# Sheet1.net
KiCad netlist of a schematic drawn in Altium Designer
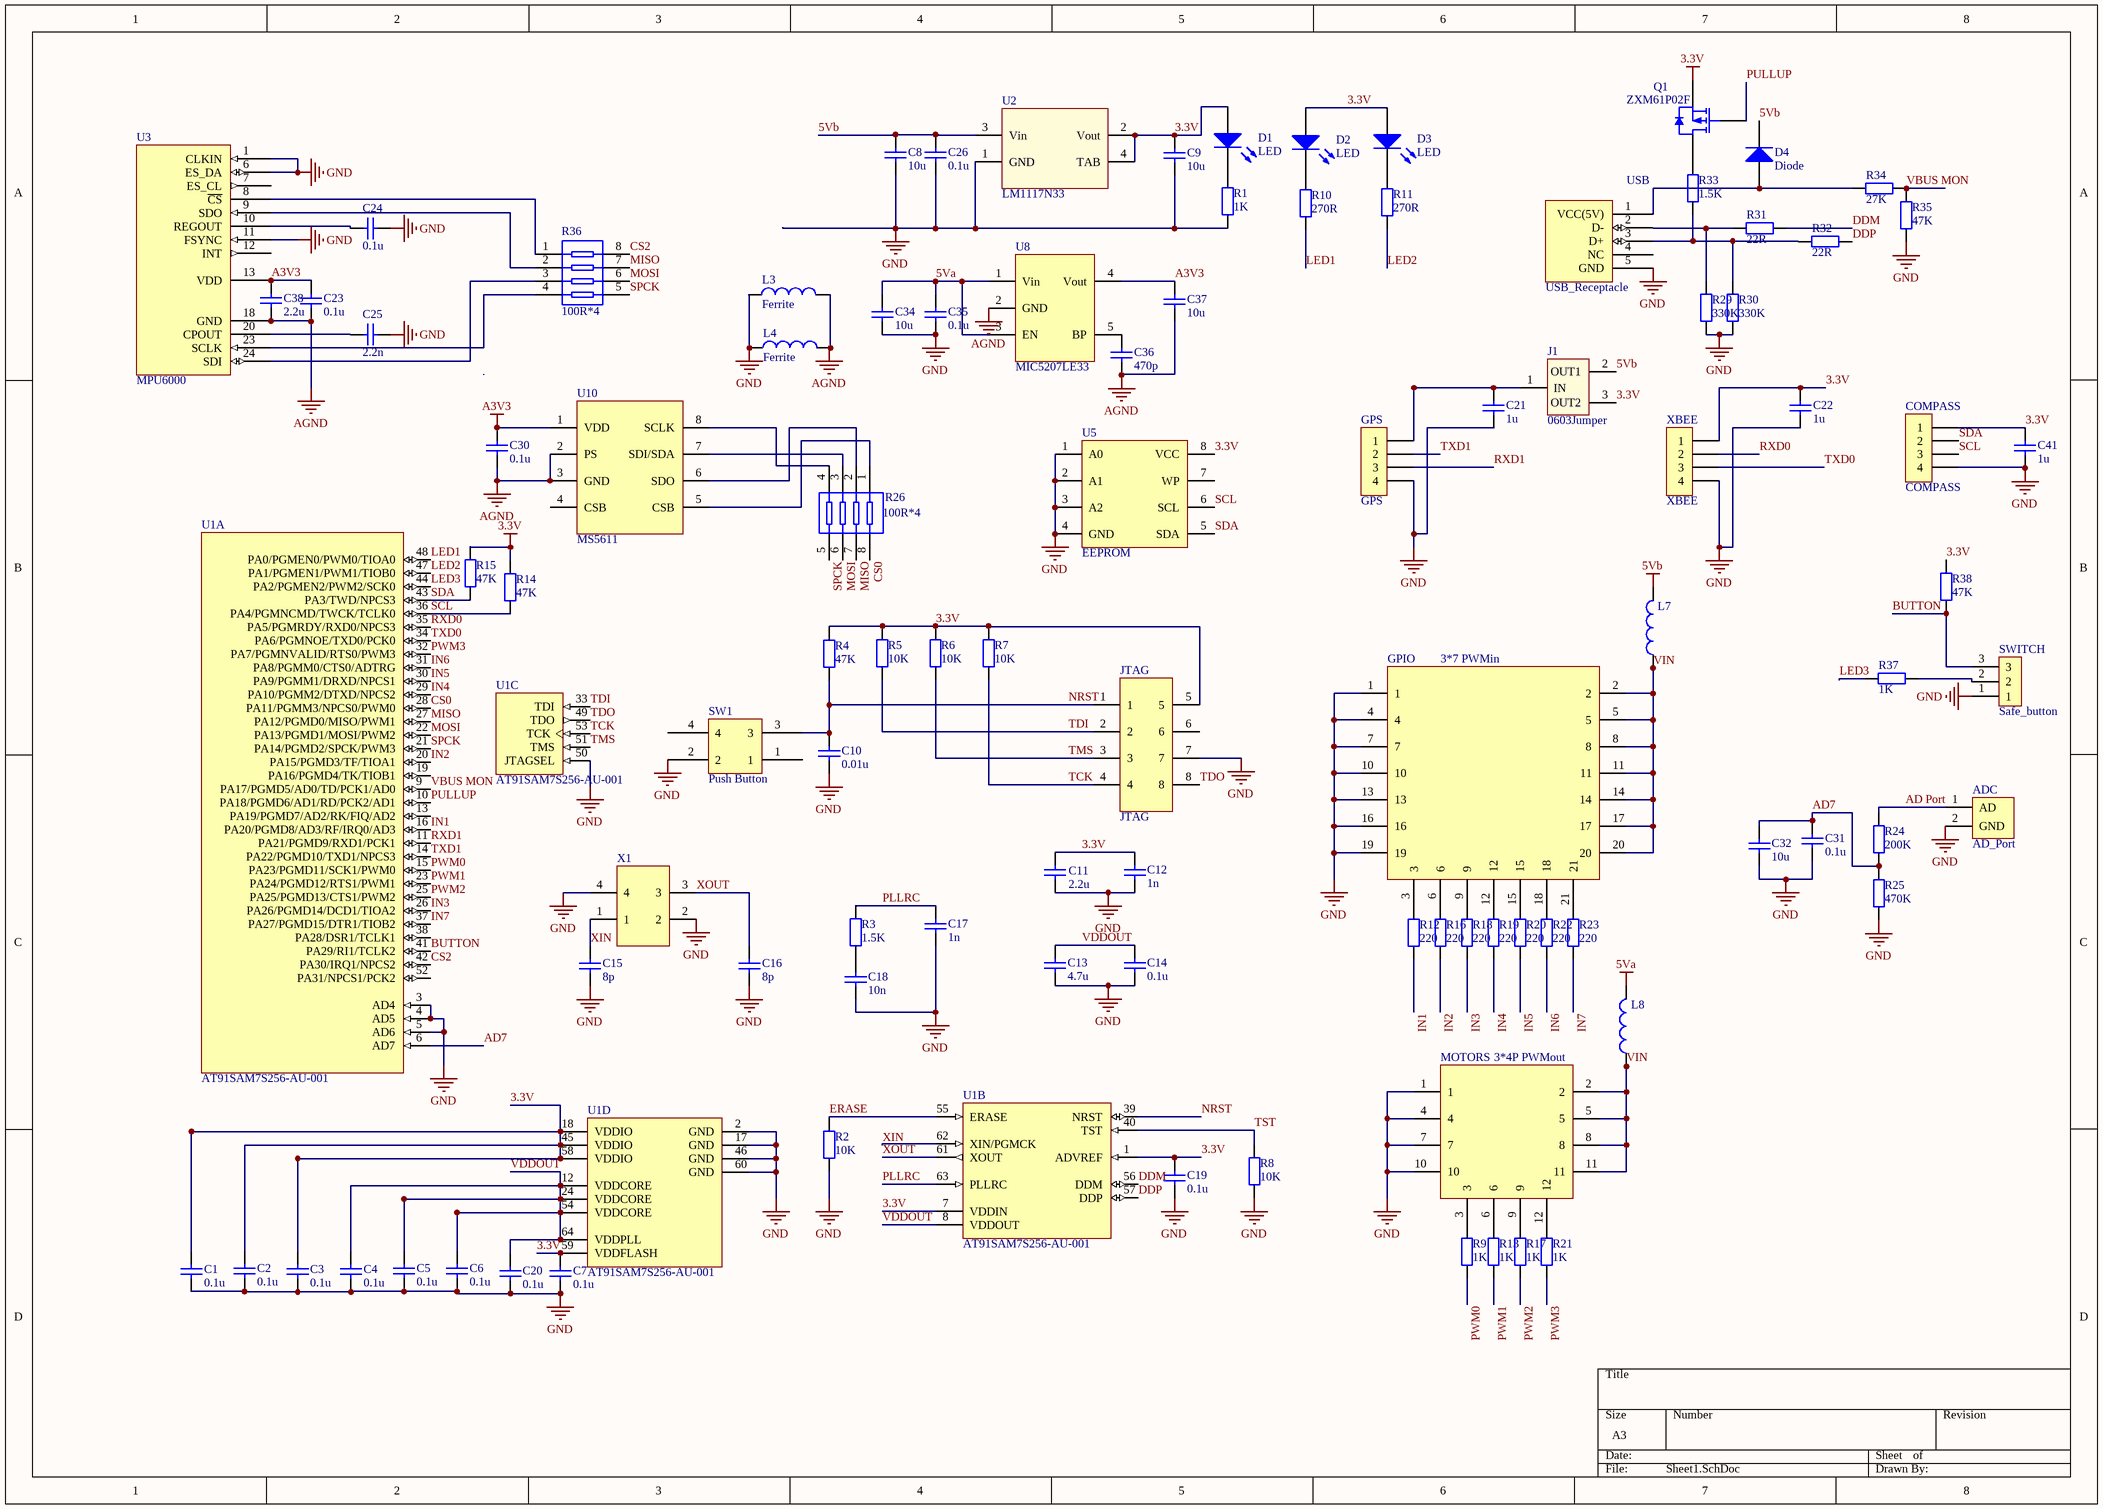
[diagram p0: Sheet1.SchDoc]

(export (version "E")
  (design (tool "Eeschema 10.0.6"))
  (components
    (comp (ref "ADC")
      (value "AD_Port")
      (footprint "2P_1.25mm（贴片）")
      (libsource (lib "Schlib1") (part "AD_Port"))
    )
    (comp (ref "C1")
      (value "0.1u")
      (footprint "1608[0603]")
      (description "0603 Capacitor")
      (fields (field (name "PUBLISHER") "Altium Limited"))
      (libsource (lib "Schlib1") (part "Cap 0603"))
    )
    (comp (ref "C2")
      (value "0.1u")
      (footprint "1608[0603]")
      (description "0603 Capacitor")
      (fields (field (name "PUBLISHER") "Altium Limited"))
      (libsource (lib "Schlib1") (part "Cap 0603"))
    )
    (comp (ref "C3")
      (value "0.1u")
      (footprint "1608[0603]")
      (description "0603 Capacitor")
      (fields (field (name "PUBLISHER") "Altium Limited"))
      (libsource (lib "Schlib1") (part "Cap 0603"))
    )
    (comp (ref "C4")
      (value "0.1u")
      (footprint "1608[0603]")
      (description "0603 Capacitor")
      (fields (field (name "PUBLISHER") "Altium Limited"))
      (libsource (lib "Schlib1") (part "Cap 0603"))
    )
    (comp (ref "C5")
      (value "0.1u")
      (footprint "1608[0603]")
      (description "0603 Capacitor")
      (fields (field (name "PUBLISHER") "Altium Limited"))
      (libsource (lib "Schlib1") (part "Cap 0603"))
    )
    (comp (ref "C6")
      (value "0.1u")
      (footprint "1608[0603]")
      (description "0603 Capacitor")
      (fields (field (name "PUBLISHER") "Altium Limited"))
      (libsource (lib "Schlib1") (part "Cap 0603"))
    )
    (comp (ref "C7")
      (value "0.1u")
      (footprint "1608[0603]")
      (description "0603 Capacitor")
      (fields (field (name "PUBLISHER") "Altium Limited"))
      (libsource (lib "Schlib1") (part "Cap 0603"))
    )
    (comp (ref "C8")
      (value "10u")
      (footprint "1206")
      (description "1206 Capacitor")
      (fields (field (name "PUBLISHER") "Altium Limited"))
      (libsource (lib "Schlib1") (part "Cap 1206"))
    )
    (comp (ref "C9")
      (value "10u")
      (footprint "1206")
      (description "1206 Capacitor")
      (fields (field (name "PUBLISHER") "Altium Limited"))
      (libsource (lib "Schlib1") (part "Cap 1206"))
    )
    (comp (ref "C10")
      (value "0.01u")
      (footprint "1608[0603]")
      (description "0603 Capacitor")
      (fields (field (name "PUBLISHER") "Altium Limited"))
      (libsource (lib "Schlib1") (part "Cap 0603"))
    )
    (comp (ref "C11")
      (value "2.2u")
      (footprint "0805")
      (description "0805 Capacitor")
      (fields (field (name "PUBLISHER") "Altium Limited"))
      (libsource (lib "Schlib1") (part "Cap 0805"))
    )
    (comp (ref "C12")
      (value "1n")
      (footprint "1608[0603]")
      (description "0603 Capacitor")
      (fields (field (name "PUBLISHER") "Altium Limited"))
      (libsource (lib "Schlib1") (part "Cap 0603"))
    )
    (comp (ref "C13")
      (value "4.7u")
      (footprint "0805")
      (description "0805 Capacitor")
      (fields (field (name "PUBLISHER") "Altium Limited"))
      (libsource (lib "Schlib1") (part "Cap 0805"))
    )
    (comp (ref "C14")
      (value "0.1u")
      (footprint "1608[0603]")
      (description "0603 Capacitor")
      (fields (field (name "PUBLISHER") "Altium Limited"))
      (libsource (lib "Schlib1") (part "Cap 0603"))
    )
    (comp (ref "C15")
      (value "8p")
      (footprint "1608[0603]")
      (description "0603 Capacitor")
      (fields (field (name "PUBLISHER") "Altium Limited"))
      (libsource (lib "Schlib1") (part "Cap 0603"))
    )
    (comp (ref "C16")
      (value "8p")
      (footprint "1608[0603]")
      (description "0603 Capacitor")
      (fields (field (name "PUBLISHER") "Altium Limited"))
      (libsource (lib "Schlib1") (part "Cap 0603"))
    )
    (comp (ref "C17")
      (value "1n")
      (footprint "1608[0603]")
      (description "0603 Capacitor")
      (fields (field (name "PUBLISHER") "Altium Limited"))
      (libsource (lib "Schlib1") (part "Cap 0603"))
    )
    (comp (ref "C18")
      (value "10n")
      (footprint "1608[0603]")
      (description "0603 Capacitor")
      (fields (field (name "PUBLISHER") "Altium Limited"))
      (libsource (lib "Schlib1") (part "Cap 0603"))
    )
    (comp (ref "C19")
      (value "0.1u")
      (footprint "1608[0603]")
      (description "0603 Capacitor")
      (fields (field (name "PUBLISHER") "Altium Limited"))
      (libsource (lib "Schlib1") (part "Cap 0603"))
    )
    (comp (ref "C20")
      (value "0.1u")
      (footprint "1608[0603]")
      (description "0603 Capacitor")
      (fields (field (name "PUBLISHER") "Altium Limited"))
      (libsource (lib "Schlib1") (part "Cap 0603"))
    )
    (comp (ref "C21")
      (value "1u")
      (footprint "1608[0603]")
      (description "0603 Capacitor")
      (fields (field (name "PUBLISHER") "Altium Limited"))
      (libsource (lib "Schlib1") (part "Cap 0603"))
    )
    (comp (ref "C22")
      (value "1u")
      (footprint "1608[0603]")
      (description "0603 Capacitor")
      (fields (field (name "PUBLISHER") "Altium Limited"))
      (libsource (lib "Schlib1") (part "Cap 0603"))
    )
    (comp (ref "C23")
      (value "0.1u")
      (footprint "1608[0603]")
      (description "0603 Capacitor")
      (fields (field (name "PUBLISHER") "Altium Limited"))
      (libsource (lib "Schlib1") (part "Cap 0603"))
    )
    (comp (ref "C24")
      (value "0.1u")
      (footprint "1608[0603]")
      (description "0603 Capacitor")
      (fields (field (name "PUBLISHER") "Altium Limited"))
      (libsource (lib "Schlib1") (part "Cap 0603"))
    )
    (comp (ref "C25")
      (value "2.2n")
      (footprint "1608[0603]")
      (description "0603 Capacitor")
      (fields (field (name "PUBLISHER") "Altium Limited"))
      (libsource (lib "Schlib1") (part "Cap 0603"))
    )
    (comp (ref "C26")
      (value "0.1u")
      (footprint "1608[0603]")
      (description "1206 Capacitor")
      (fields (field (name "PUBLISHER") "Altium Limited"))
      (libsource (lib "Schlib1") (part "Cap 1206"))
    )
    (comp (ref "C30")
      (value "0.1u")
      (footprint "1608[0603]")
      (description "0603 Capacitor")
      (fields (field (name "PUBLISHER") "Altium Limited"))
      (libsource (lib "Schlib1") (part "Cap 0603"))
    )
    (comp (ref "C31")
      (value "0.1u")
      (footprint "1608[0603]")
      (description "0603 Capacitor")
      (fields (field (name "PUBLISHER") "Altium Limited"))
      (libsource (lib "Schlib1") (part "Cap 0603"))
    )
    (comp (ref "C32")
      (value "10u")
      (footprint "1206")
      (description "1206 Capacitor")
      (fields (field (name "PUBLISHER") "Altium Limited"))
      (libsource (lib "Schlib1") (part "Cap 1206"))
    )
    (comp (ref "C34")
      (value "10u")
      (footprint "1206")
      (description "1206 Capacitor")
      (fields (field (name "PUBLISHER") "Altium Limited"))
      (libsource (lib "Schlib1") (part "Cap 1206"))
    )
    (comp (ref "C35")
      (value "0.1u")
      (footprint "1608[0603]")
      (description "0603 Capacitor")
      (fields (field (name "PUBLISHER") "Altium Limited"))
      (libsource (lib "Schlib1") (part "Cap 0603"))
    )
    (comp (ref "C36")
      (value "470p")
      (footprint "1608[0603]")
      (description "0603 Capacitor")
      (fields (field (name "PUBLISHER") "Altium Limited"))
      (libsource (lib "Schlib1") (part "Cap 0603"))
    )
    (comp (ref "C37")
      (value "10u")
      (footprint "1206")
      (description "0603 Capacitor")
      (fields (field (name "PUBLISHER") "Altium Limited"))
      (libsource (lib "Schlib1") (part "Cap 0603"))
    )
    (comp (ref "C38")
      (value "2.2u")
      (footprint "1608[0603]")
      (description "0603 Capacitor")
      (fields (field (name "PUBLISHER") "Altium Limited"))
      (libsource (lib "Schlib1") (part "Cap 0603"))
    )
    (comp (ref "C41")
      (value "1u")
      (footprint "1608[0603]")
      (description "0603 Capacitor")
      (fields (field (name "PUBLISHER") "Altium Limited"))
      (libsource (lib "Schlib1") (part "Cap 0603"))
    )
    (comp (ref "COMPASS")
      (value "COMPASS")
      (footprint "4P_1.25mm（贴片）")
      (description "Header, 4-Pin")
      (fields (field (name "PUBLISHER") "Altium Limited"))
      (libsource (lib "Schlib1") (part "COMPASS"))
    )
    (comp (ref "D1")
      (value "LED")
      (footprint "LED")
      (description "Typical RED, GREEN, YELLOW, AMBER GaAs LED")
      (fields (field (name "PUBLISHER") "Altium Limited"))
      (libsource (lib "Schlib1") (part "LED"))
    )
    (comp (ref "D2")
      (value "LED")
      (footprint "LED")
      (description "Typical RED, GREEN, YELLOW, AMBER GaAs LED")
      (fields (field (name "PUBLISHER") "Altium Limited"))
      (libsource (lib "Schlib1") (part "LED"))
    )
    (comp (ref "D3")
      (value "LED")
      (footprint "LED")
      (description "Typical RED, GREEN, YELLOW, AMBER GaAs LED")
      (fields (field (name "PUBLISHER") "Altium Limited"))
      (libsource (lib "Schlib1") (part "LED"))
    )
    (comp (ref "D4")
      (value "Diode")
      (footprint "1206")
      (description "Default Diode")
      (fields (field (name "PUBLISHER") "Altium Limited"))
      (libsource (lib "Schlib1") (part "Diode"))
    )
    (comp (ref "GPIO")
      (value "3*7 PWMin")
      (footprint "HEADER3X7")
      (libsource (lib "Schlib1") (part "MyPWMin"))
    )
    (comp (ref "GPS")
      (value "GPS")
      (footprint "6P_PH1.25mm（贴片）")
      (description "Header, 4-Pin")
      (fields (field (name "PUBLISHER") "Altium Limited"))
      (libsource (lib "Schlib1") (part "GPS"))
    )
    (comp (ref "J1")
      (value "0603Jumper")
      (footprint "1-2Jumper")
      (libsource (lib "Schlib1") (part "0603Jumper"))
    )
    (comp (ref "JTAG") (value "JTAG") (footprint "JTAG2") (libsource (lib "Schlib1") (part "JTAG2")))
    (comp (ref "L3")
      (value "Ferrite")
      (footprint "1608[0603]")
      (description "Inductor")
      (fields (field (name "PUBLISHER") "Altium Limited"))
      (libsource (lib "Schlib1") (part "Inductor"))
    )
    (comp (ref "L4")
      (value "Ferrite")
      (footprint "1608[0603]")
      (description "Inductor")
      (fields (field (name "PUBLISHER") "Altium Limited"))
      (libsource (lib "Schlib1") (part "Inductor"))
    )
    (comp (ref "L7")
      (value "~")
      (footprint "1608[0603]")
      (description "Inductor")
      (fields (field (name "PUBLISHER") "Altium Limited"))
      (libsource (lib "Schlib1") (part "Inductor"))
    )
    (comp (ref "L8")
      (value "~")
      (footprint "1608[0603]")
      (description "Inductor")
      (fields (field (name "PUBLISHER") "Altium Limited"))
      (libsource (lib "Schlib1") (part "Inductor"))
    )
    (comp (ref "MOTORS")
      (value "3*4P PWMout")
      (footprint "header3x4")
      (libsource (lib "Schlib1") (part "MyPWMout"))
    )
    (comp (ref "Q1")
      (value "ZXM61P02F")
      (footprint "SOT23")
      (description "20V P-Channel Enhancement Mode MOSFET")
      (fields (field (name "PUBLISHER") "Altium Limited"))
      (libsource (lib "Schlib1") (part "ZXM61P02F"))
    )
    (comp (ref "R1")
      (value "1K")
      (footprint "1608[0603]")
      (description "Resistor")
      (fields (field (name "PUBLISHER") "Altium Limited"))
      (libsource (lib "Schlib1") (part "Res 0603"))
    )
    (comp (ref "R2")
      (value "10K")
      (footprint "1608[0603]")
      (description "Resistor")
      (fields (field (name "PUBLISHER") "Altium Limited"))
      (libsource (lib "Schlib1") (part "Res 0603"))
    )
    (comp (ref "R3")
      (value "1.5K")
      (footprint "1608[0603]")
      (description "Resistor")
      (fields (field (name "PUBLISHER") "Altium Limited"))
      (libsource (lib "Schlib1") (part "Res 0603"))
    )
    (comp (ref "R4")
      (value "47K")
      (footprint "1608[0603]")
      (description "Resistor")
      (fields (field (name "PUBLISHER") "Altium Limited"))
      (libsource (lib "Schlib1") (part "Res 0603"))
    )
    (comp (ref "R5")
      (value "10K")
      (footprint "1608[0603]")
      (description "Resistor")
      (fields (field (name "PUBLISHER") "Altium Limited"))
      (libsource (lib "Schlib1") (part "Res 0603"))
    )
    (comp (ref "R6")
      (value "10K")
      (footprint "1608[0603]")
      (description "Resistor")
      (fields (field (name "PUBLISHER") "Altium Limited"))
      (libsource (lib "Schlib1") (part "Res 0603"))
    )
    (comp (ref "R7")
      (value "10K")
      (footprint "1608[0603]")
      (description "Resistor")
      (fields (field (name "PUBLISHER") "Altium Limited"))
      (libsource (lib "Schlib1") (part "Res 0603"))
    )
    (comp (ref "R8")
      (value "10K")
      (footprint "1608[0603]")
      (description "Resistor")
      (fields (field (name "PUBLISHER") "Altium Limited"))
      (libsource (lib "Schlib1") (part "Res 0603"))
    )
    (comp (ref "R9")
      (value "1K")
      (footprint "1608[0603]")
      (description "Resistor")
      (libsource (lib "Schlib1") (part "Res 0603"))
    )
    (comp (ref "R10")
      (value "270R")
      (footprint "1608[0603]")
      (description "Resistor")
      (fields (field (name "PUBLISHER") "Altium Limited"))
      (libsource (lib "Schlib1") (part "Res 0603"))
    )
    (comp (ref "R11")
      (value "270R")
      (footprint "1608[0603]")
      (description "Resistor")
      (fields (field (name "PUBLISHER") "Altium Limited"))
      (libsource (lib "Schlib1") (part "Res 0603"))
    )
    (comp (ref "R12")
      (value "220")
      (footprint "1608[0603]")
      (description "Resistor")
      (fields (field (name "PUBLISHER") "Altium Limited"))
      (libsource (lib "Schlib1") (part "Res 0603"))
    )
    (comp (ref "R13")
      (value "1K")
      (footprint "1608[0603]")
      (description "Resistor")
      (libsource (lib "Schlib1") (part "Res 0603"))
    )
    (comp (ref "R14")
      (value "47K")
      (footprint "1608[0603]")
      (description "Resistor")
      (fields (field (name "PUBLISHER") "Altium Limited"))
      (libsource (lib "Schlib1") (part "Res 0603"))
    )
    (comp (ref "R15")
      (value "47K")
      (footprint "1608[0603]")
      (description "Resistor")
      (fields (field (name "PUBLISHER") "Altium Limited"))
      (libsource (lib "Schlib1") (part "Res 0603"))
    )
    (comp (ref "R16")
      (value "220")
      (footprint "1608[0603]")
      (description "Resistor")
      (fields (field (name "PUBLISHER") "Altium Limited"))
      (libsource (lib "Schlib1") (part "Res 0603"))
    )
    (comp (ref "R17")
      (value "1K")
      (footprint "1608[0603]")
      (description "Resistor")
      (libsource (lib "Schlib1") (part "Res 0603"))
    )
    (comp (ref "R18")
      (value "220")
      (footprint "1608[0603]")
      (description "Resistor")
      (fields (field (name "PUBLISHER") "Altium Limited"))
      (libsource (lib "Schlib1") (part "Res 0603"))
    )
    (comp (ref "R19")
      (value "220")
      (footprint "1608[0603]")
      (description "Resistor")
      (fields (field (name "PUBLISHER") "Altium Limited"))
      (libsource (lib "Schlib1") (part "Res 0603"))
    )
    (comp (ref "R20")
      (value "220")
      (footprint "1608[0603]")
      (description "Resistor")
      (fields (field (name "PUBLISHER") "Altium Limited"))
      (libsource (lib "Schlib1") (part "Res 0603"))
    )
    (comp (ref "R21")
      (value "1K")
      (footprint "1608[0603]")
      (description "Resistor")
      (libsource (lib "Schlib1") (part "Res 0603"))
    )
    (comp (ref "R22")
      (value "220")
      (footprint "1608[0603]")
      (description "Resistor")
      (fields (field (name "PUBLISHER") "Altium Limited"))
      (libsource (lib "Schlib1") (part "Res 0603"))
    )
    (comp (ref "R23")
      (value "220")
      (footprint "1608[0603]")
      (description "Resistor")
      (fields (field (name "PUBLISHER") "Altium Limited"))
      (libsource (lib "Schlib1") (part "Res 0603"))
    )
    (comp (ref "R24")
      (value "200K")
      (footprint "1608[0603]")
      (description "Resistor")
      (fields (field (name "PUBLISHER") "Altium Limited"))
      (libsource (lib "Schlib1") (part "Res 0603"))
    )
    (comp (ref "R25")
      (value "470K")
      (footprint "1608[0603]")
      (description "Resistor")
      (fields (field (name "PUBLISHER") "Altium Limited"))
      (libsource (lib "Schlib1") (part "Res 0603"))
    )
    (comp (ref "R26")
      (value "100R*4")
      (footprint "Resistances")
      (description "Isolated Resistor Network")
      (fields (field (name "PUBLISHER") "Altium Limited"))
      (libsource (lib "Schlib1") (part "Res Pack4"))
    )
    (comp (ref "R29")
      (value "330K")
      (footprint "1608[0603]")
      (description "Resistor")
      (fields (field (name "PUBLISHER") "Altium Limited"))
      (libsource (lib "") (part "Res 0603_3"))
    )
    (comp (ref "R30")
      (value "330K")
      (footprint "1608[0603]")
      (description "Resistor")
      (fields (field (name "PUBLISHER") "Altium Limited"))
      (libsource (lib "") (part "Res 0603_3"))
    )
    (comp (ref "R31")
      (value "22R")
      (footprint "1608[0603]")
      (description "Resistor")
      (fields (field (name "PUBLISHER") "Altium Limited"))
      (libsource (lib "") (part "Res 0603_1"))
    )
    (comp (ref "R32")
      (value "22R")
      (footprint "1608[0603]")
      (description "Resistor")
      (fields (field (name "PUBLISHER") "Altium Limited"))
      (libsource (lib "") (part "Res 0603_1"))
    )
    (comp (ref "R33")
      (value "1.5K")
      (footprint "1608[0603]")
      (description "Resistor")
      (fields (field (name "PUBLISHER") "Altium Limited"))
      (libsource (lib "") (part "Res 0603_3"))
    )
    (comp (ref "R34")
      (value "27K")
      (footprint "1608[0603]")
      (description "Resistor")
      (fields (field (name "PUBLISHER") "Altium Limited"))
      (libsource (lib "") (part "Res 0603_1"))
    )
    (comp (ref "R35")
      (value "47K")
      (footprint "1608[0603]")
      (description "Resistor")
      (fields (field (name "PUBLISHER") "Altium Limited"))
      (libsource (lib "Schlib1") (part "Res 0603"))
    )
    (comp (ref "R36")
      (value "100R*4")
      (footprint "ResPack")
      (description "Isolated Resistor Network")
      (fields (field (name "PUBLISHER") "Altium Limited"))
      (libsource (lib "Schlib1") (part "Res Pack4"))
    )
    (comp (ref "R37")
      (value "1K")
      (footprint "1608[0603]")
      (description "Resistor")
      (fields (field (name "PUBLISHER") "Altium Limited"))
      (libsource (lib "") (part "Res 0603_2"))
    )
    (comp (ref "R38")
      (value "47K")
      (footprint "1608[0603]")
      (description "Resistor")
      (fields (field (name "PUBLISHER") "Altium Limited"))
      (libsource (lib "Schlib1") (part "Res 0603"))
    )
    (comp (ref "SW1")
      (value "Push Button")
      (footprint "switch")
      (libsource (lib "Schlib1") (part "Push Button"))
    )
    (comp (ref "SWITCH")
      (value "Safe_button")
      (footprint "3P_1.25mm（贴片）")
      (libsource (lib "Schlib1") (part "Safe_button"))
    )
    (comp (ref "U1")
      (value "AT91SAM7S256-AU-001")
      (footprint "LQFP64_N")
      (fields (field (name "PUBLISHER") "Altium Limited"))
      (libsource (lib "Atmel Microcontroller 32-Bit ARM") (part "AT91SAM7S256-AU-001"))
    )
    (comp (ref "U2")
      (value "LM1117N33")
      (footprint "SOT230P700X180-4N")
      (description "3.3V Regulator")
      (libsource (lib "Schlib1") (part "LM1117S33"))
    )
    (comp (ref "U3") (value "MPU6000") (footprint "LGANEW") (libsource (lib "Schlib1") (part "MPU6000")))
    (comp (ref "U5") (value "EEPROM") (footprint "EEPROM") (libsource (lib "Schlib1") (part "ROM")))
    (comp (ref "U8") (value "MIC5207LE33") (footprint "S5") (libsource (lib "Schlib1") (part "MIC5207")))
    (comp (ref "U10") (value "MS5611") (footprint "MS_5611") (libsource (lib "Schlib1") (part "MS5611")))
    (comp (ref "USB")
      (value "USB_Receptacle")
      (footprint "micro_usb")
      (libsource (lib "Schlib1") (part "USB_Receptacle"))
    )
    (comp (ref "X1") (value "~") (footprint "OSC2") (libsource (lib "Schlib1") (part "OSC2")))
    (comp (ref "XBEE")
      (value "XBEE")
      (footprint "4P_1.25mm（贴片）")
      (description "Header, 4-Pin")
      (fields (field (name "PUBLISHER") "Altium Limited"))
      (libsource (lib "Schlib1") (part "XBEE"))
    )
  )
  (nets
    (net (code "1") (name "/AD Port") (class "Default")
      (node (ref "ADC") (pin "1") (pinfunction "AD_1") (pintype "passive"))
      (node (ref "R24") (pin "2") (pinfunction "2_2") (pintype "passive"))
    )
    (net (code "2") (name "/AD7") (class "Default")
      (node (ref "C31") (pin "2") (pinfunction "2_2") (pintype "passive"))
      (node (ref "C32") (pin "2") (pinfunction "2_2") (pintype "passive"))
      (node (ref "R24") (pin "1") (pinfunction "1_1") (pintype "passive"))
      (node (ref "R25") (pin "2") (pinfunction "2_2") (pintype "passive"))
      (node (ref "U1") (pin "6") (pinfunction "AD7_6") (pintype "input"))
    )
    (net (code "3") (name "/BUTTON") (class "Default")
      (node (ref "R38") (pin "1") (pinfunction "1_1") (pintype "passive"))
      (node (ref "SWITCH") (pin "3") (pinfunction "3_3") (pintype "passive"))
      (node (ref "U1") (pin "41") (pinfunction "PA29/RI1/TCLK2_41") (pintype "bidirectional"))
    )
    (net (code "4") (name "/CS0") (class "Default")
      (node (ref "R26") (pin "8") (pinfunction "8_8") (pintype "passive"))
      (node (ref "U1") (pin "28") (pinfunction "PA11/PGMM3/NPCS0/PWM0_28") (pintype "bidirectional"))
    )
    (net (code "5") (name "/CS2") (class "Default")
      (node (ref "R36") (pin "8") (pinfunction "8_8") (pintype "passive"))
      (node (ref "U1") (pin "42") (pinfunction "PA30/IRQ1/NPCS2_42") (pintype "bidirectional"))
    )
    (net (code "6") (name "/DDM") (class "Default")
      (node (ref "R31") (pin "2") (pinfunction "2_2") (pintype "passive"))
      (node (ref "U1") (pin "56") (pinfunction "DDM_56") (pintype "bidirectional"))
    )
    (net (code "7") (name "/DDP") (class "Default")
      (node (ref "R32") (pin "2") (pinfunction "2_2") (pintype "passive"))
      (node (ref "U1") (pin "57") (pinfunction "DDP_57") (pintype "bidirectional"))
    )
    (net (code "8") (name "/ERASE") (class "Default")
      (node (ref "R2") (pin "2") (pinfunction "2_2") (pintype "passive"))
      (node (ref "U1") (pin "55") (pinfunction "ERASE_55") (pintype "input"))
    )
    (net (code "9") (name "/IN1") (class "Default")
      (node (ref "R12") (pin "1") (pinfunction "1_1") (pintype "passive"))
      (node (ref "U1") (pin "16") (pinfunction "PA20/PGMD8/AD3/RF/IRQ0/AD3_16") (pintype "bidirectional"))
    )
    (net (code "10") (name "/IN2") (class "Default")
      (node (ref "R16") (pin "1") (pinfunction "1_1") (pintype "passive"))
      (node (ref "U1") (pin "20") (pinfunction "PA15/PGMD3/TF/TIOA1_20") (pintype "bidirectional"))
    )
    (net (code "11") (name "/IN3") (class "Default")
      (node (ref "R18") (pin "1") (pinfunction "1_1") (pintype "passive"))
      (node (ref "U1") (pin "26") (pinfunction "PA26/PGMD14/DCD1/TIOA2_26") (pintype "bidirectional"))
    )
    (net (code "12") (name "/IN4") (class "Default")
      (node (ref "R19") (pin "1") (pinfunction "1_1") (pintype "passive"))
      (node (ref "U1") (pin "29") (pinfunction "PA10/PGMM2/DTXD/NPCS2_29") (pintype "bidirectional"))
    )
    (net (code "13") (name "/IN5") (class "Default")
      (node (ref "R20") (pin "1") (pinfunction "1_1") (pintype "passive"))
      (node (ref "U1") (pin "30") (pinfunction "PA9/PGMM1/DRXD/NPCS1_30") (pintype "bidirectional"))
    )
    (net (code "14") (name "/IN6") (class "Default")
      (node (ref "R22") (pin "1") (pinfunction "1_1") (pintype "passive"))
      (node (ref "U1") (pin "31") (pinfunction "PA8/PGMM0/CTS0/ADTRG_31") (pintype "bidirectional"))
    )
    (net (code "15") (name "/IN7") (class "Default")
      (node (ref "R23") (pin "1") (pinfunction "1_1") (pintype "passive"))
      (node (ref "U1") (pin "37") (pinfunction "PA27/PGMD15/DTR1/TIOB2_37") (pintype "bidirectional"))
    )
    (net (code "16") (name "/LED1") (class "Default")
      (node (ref "R10") (pin "1") (pinfunction "1_1") (pintype "passive"))
      (node (ref "U1") (pin "48") (pinfunction "PA0/PGMEN0/PWM0/TIOA0_48") (pintype "bidirectional"))
    )
    (net (code "17") (name "/LED2") (class "Default")
      (node (ref "R11") (pin "1") (pinfunction "1_1") (pintype "passive"))
      (node (ref "U1") (pin "47") (pinfunction "PA1/PGMEN1/PWM1/TIOB0_47") (pintype "bidirectional"))
    )
    (net (code "18") (name "/LED3") (class "Default")
      (node (ref "R37") (pin "2") (pinfunction "2_2") (pintype "passive"))
      (node (ref "U1") (pin "44") (pinfunction "PA2/PGMEN2/PWM2/SCK0_44") (pintype "bidirectional"))
    )
    (net (code "19") (name "/MISO") (class "Default")
      (node (ref "R26") (pin "7") (pinfunction "7_7") (pintype "passive"))
      (node (ref "R36") (pin "7") (pinfunction "7_7") (pintype "passive"))
      (node (ref "U1") (pin "27") (pinfunction "PA12/PGMD0/MISO/PWM1_27") (pintype "bidirectional"))
    )
    (net (code "20") (name "/MOSI") (class "Default")
      (node (ref "R26") (pin "6") (pinfunction "6_6") (pintype "passive"))
      (node (ref "R36") (pin "6") (pinfunction "6_6") (pintype "passive"))
      (node (ref "U1") (pin "22") (pinfunction "PA13/PGMD1/MOSI/PWM2_22") (pintype "bidirectional"))
    )
    (net (code "21") (name "/NRST") (class "Default")
      (node (ref "C10") (pin "2") (pinfunction "2_2") (pintype "passive"))
      (node (ref "JTAG") (pin "1") (pinfunction "1_1") (pintype "passive"))
      (node (ref "R4") (pin "1") (pinfunction "1_1") (pintype "passive"))
      (node (ref "SW1") (pin "3") (pinfunction "3_3") (pintype "passive"))
      (node (ref "U1") (pin "39") (pinfunction "NRST_39") (pintype "bidirectional"))
    )
    (net (code "22") (name "/PLLRC") (class "Default")
      (node (ref "C17") (pin "2") (pinfunction "2_2") (pintype "passive"))
      (node (ref "R3") (pin "2") (pinfunction "2_2") (pintype "passive"))
      (node (ref "U1") (pin "63") (pinfunction "PLLRC_63") (pintype "input"))
    )
    (net (code "23") (name "/PULLUP") (class "Default")
      (node (ref "Q1") (pin "3") (pinfunction "G_3") (pintype "passive"))
      (node (ref "U1") (pin "10") (pinfunction "PA18/PGMD6/AD1/RD/PCK2/AD1_10") (pintype "bidirectional"))
    )
    (net (code "24") (name "/PWM0") (class "Default")
      (node (ref "R9") (pin "1") (pinfunction "1_1") (pintype "passive"))
      (node (ref "U1") (pin "15") (pinfunction "PA23/PGMD11/SCK1/PWM0_15") (pintype "bidirectional"))
    )
    (net (code "25") (name "/PWM1") (class "Default")
      (node (ref "R13") (pin "1") (pinfunction "1_1") (pintype "passive"))
      (node (ref "U1") (pin "23") (pinfunction "PA24/PGMD12/RTS1/PWM1_23") (pintype "bidirectional"))
    )
    (net (code "26") (name "/PWM2") (class "Default")
      (node (ref "R17") (pin "1") (pinfunction "1_1") (pintype "passive"))
      (node (ref "U1") (pin "25") (pinfunction "PA25/PGMD13/CTS1/PWM2_25") (pintype "bidirectional"))
    )
    (net (code "27") (name "/PWM3") (class "Default")
      (node (ref "R21") (pin "1") (pinfunction "1_1") (pintype "passive"))
      (node (ref "U1") (pin "32") (pinfunction "PA7/PGMNVALID/RTS0/PWM3_32") (pintype "bidirectional"))
    )
    (net (code "28") (name "/RXD0") (class "Default")
      (node (ref "U1") (pin "35") (pinfunction "PA5/PGMRDY/RXD0/NPCS3_35") (pintype "bidirectional"))
      (node (ref "XBEE") (pin "2") (pinfunction "2_2") (pintype "passive"))
    )
    (net (code "29") (name "/RXD1") (class "Default")
      (node (ref "GPS") (pin "3") (pinfunction "3_3") (pintype "passive"))
      (node (ref "U1") (pin "11") (pinfunction "PA21/PGMD9/RXD1/PCK1_11") (pintype "bidirectional"))
    )
    (net (code "30") (name "/SCL") (class "Default")
      (node (ref "COMPASS") (pin "3") (pinfunction "3_3") (pintype "passive"))
      (node (ref "R14") (pin "1") (pinfunction "1_1") (pintype "passive"))
      (node (ref "U1") (pin "36") (pinfunction "PA4/PGMNCMD/TWCK/TCLK0_36") (pintype "bidirectional"))
      (node (ref "U5") (pin "6") (pinfunction "SCL_6") (pintype "passive"))
    )
    (net (code "31") (name "/SDA") (class "Default")
      (node (ref "COMPASS") (pin "2") (pinfunction "2_2") (pintype "passive"))
      (node (ref "R15") (pin "1") (pinfunction "1_1") (pintype "passive"))
      (node (ref "U1") (pin "43") (pinfunction "PA3/TWD/NPCS3_43") (pintype "bidirectional"))
      (node (ref "U5") (pin "5") (pinfunction "SDA_5") (pintype "passive"))
    )
    (net (code "32") (name "/SPCK") (class "Default")
      (node (ref "R26") (pin "5") (pinfunction "5_5") (pintype "passive"))
      (node (ref "R36") (pin "5") (pinfunction "5_5") (pintype "passive"))
      (node (ref "U1") (pin "21") (pinfunction "PA14/PGMD2/SPCK/PWM3_21") (pintype "bidirectional"))
    )
    (net (code "33") (name "/TCK") (class "Default")
      (node (ref "JTAG") (pin "4") (pinfunction "4_4") (pintype "passive"))
      (node (ref "R7") (pin "1") (pinfunction "1_1") (pintype "passive"))
      (node (ref "U1") (pin "53") (pinfunction "TCK_53") (pintype "input"))
    )
    (net (code "34") (name "/TDI") (class "Default")
      (node (ref "JTAG") (pin "2") (pinfunction "2_2") (pintype "passive"))
      (node (ref "R5") (pin "1") (pinfunction "1_1") (pintype "passive"))
      (node (ref "U1") (pin "33") (pinfunction "TDI_33") (pintype "input"))
    )
    (net (code "35") (name "/TDO") (class "Default")
      (node (ref "JTAG") (pin "8") (pinfunction "8_8") (pintype "passive"))
      (node (ref "U1") (pin "49") (pinfunction "TDO_49") (pintype "output"))
    )
    (net (code "36") (name "/TMS") (class "Default")
      (node (ref "JTAG") (pin "3") (pinfunction "3_3") (pintype "passive"))
      (node (ref "R6") (pin "1") (pinfunction "1_1") (pintype "passive"))
      (node (ref "U1") (pin "51") (pinfunction "TMS_51") (pintype "input"))
    )
    (net (code "37") (name "/TST") (class "Default")
      (node (ref "R8") (pin "2") (pinfunction "2_2") (pintype "passive"))
      (node (ref "U1") (pin "40") (pinfunction "TST_40") (pintype "input"))
    )
    (net (code "38") (name "/TXD0") (class "Default")
      (node (ref "U1") (pin "34") (pinfunction "PA6/PGMNOE/TXD0/PCK0_34") (pintype "bidirectional"))
      (node (ref "XBEE") (pin "3") (pinfunction "3_3") (pintype "passive"))
    )
    (net (code "39") (name "/TXD1") (class "Default")
      (node (ref "GPS") (pin "2") (pinfunction "2_2") (pintype "passive"))
      (node (ref "U1") (pin "14") (pinfunction "PA22/PGMD10/TXD1/NPCS3_14") (pintype "bidirectional"))
    )
    (net (code "40") (name "/VBUS MON") (class "Default")
      (node (ref "R34") (pin "2") (pinfunction "2_2") (pintype "passive"))
      (node (ref "R35") (pin "2") (pinfunction "2_2") (pintype "passive"))
      (node (ref "U1") (pin "9") (pinfunction "PA17/PGMD5/AD0/TD/PCK1/AD0_9") (pintype "bidirectional"))
    )
    (net (code "41") (name "/VDDOUT") (class "Default")
      (node (ref "C13") (pin "2") (pinfunction "2_2") (pintype "passive"))
      (node (ref "C14") (pin "2") (pinfunction "2_2") (pintype "passive"))
      (node (ref "C20") (pin "2") (pinfunction "2_2") (pintype "passive"))
      (node (ref "C4") (pin "2") (pinfunction "2_2") (pintype "passive"))
      (node (ref "C5") (pin "2") (pinfunction "2_2") (pintype "passive"))
      (node (ref "C6") (pin "2") (pinfunction "2_2") (pintype "passive"))
      (node (ref "U1") (pin "12") (pinfunction "VDDCORE_12") (pintype "power_in"))
      (node (ref "U1") (pin "24") (pinfunction "VDDCORE_24") (pintype "power_in"))
      (node (ref "U1") (pin "54") (pinfunction "VDDCORE_54") (pintype "power_in"))
      (node (ref "U1") (pin "64") (pinfunction "VDDPLL_64") (pintype "power_in"))
      (node (ref "U1") (pin "8") (pinfunction "VDDOUT_8") (pintype "power_in"))
    )
    (net (code "42") (name "/VIN") (class "Default")
      (node (ref "GPIO") (pin "11") (pinfunction "11_11") (pintype "passive"))
      (node (ref "GPIO") (pin "14") (pinfunction "14_14") (pintype "passive"))
      (node (ref "GPIO") (pin "17") (pinfunction "17_17") (pintype "passive"))
      (node (ref "GPIO") (pin "2") (pinfunction "2_2") (pintype "passive"))
      (node (ref "GPIO") (pin "20") (pinfunction "20_20") (pintype "passive"))
      (node (ref "GPIO") (pin "5") (pinfunction "5_5") (pintype "passive"))
      (node (ref "GPIO") (pin "8") (pinfunction "8_8") (pintype "passive"))
      (node (ref "L7") (pin "1") (pinfunction "1_1") (pintype "passive"))
      (node (ref "L8") (pin "1") (pinfunction "1_1") (pintype "passive"))
      (node (ref "MOTORS") (pin "11") (pinfunction "11_11") (pintype "passive"))
      (node (ref "MOTORS") (pin "2") (pinfunction "2_2") (pintype "passive"))
      (node (ref "MOTORS") (pin "5") (pinfunction "5_5") (pintype "passive"))
      (node (ref "MOTORS") (pin "8") (pinfunction "8_8") (pintype "passive"))
    )
    (net (code "43") (name "/XIN") (class "Default")
      (node (ref "C15") (pin "2") (pinfunction "2_2") (pintype "passive"))
      (node (ref "U1") (pin "62") (pinfunction "XIN/PGMCK_62") (pintype "input"))
      (node (ref "X1") (pin "1") (pinfunction "1_1") (pintype "passive"))
    )
    (net (code "44") (name "/XOUT") (class "Default")
      (node (ref "C16") (pin "2") (pinfunction "2_2") (pintype "passive"))
      (node (ref "U1") (pin "61") (pinfunction "XOUT_61") (pintype "output"))
      (node (ref "X1") (pin "3") (pinfunction "3_3") (pintype "passive"))
    )
    (net (code "45") (name "3.3V") (class "Default")
      (node (ref "C1") (pin "2") (pinfunction "2_2") (pintype "passive"))
      (node (ref "C11") (pin "2") (pinfunction "2_2") (pintype "passive"))
      (node (ref "C12") (pin "2") (pinfunction "2_2") (pintype "passive"))
      (node (ref "C19") (pin "2") (pinfunction "2_2") (pintype "passive"))
      (node (ref "C2") (pin "2") (pinfunction "2_2") (pintype "passive"))
      (node (ref "C22") (pin "2") (pinfunction "2_2") (pintype "passive"))
      (node (ref "C3") (pin "2") (pinfunction "2_2") (pintype "passive"))
      (node (ref "C41") (pin "2") (pinfunction "2_2") (pintype "passive"))
      (node (ref "C7") (pin "2") (pinfunction "2_2") (pintype "passive"))
      (node (ref "C9") (pin "2") (pinfunction "2_2") (pintype "passive"))
      (node (ref "COMPASS") (pin "1") (pinfunction "1_1") (pintype "passive"))
      (node (ref "D1") (pin "1") (pinfunction "A_1") (pintype "passive"))
      (node (ref "D2") (pin "1") (pinfunction "A_1") (pintype "passive"))
      (node (ref "D3") (pin "1") (pinfunction "A_1") (pintype "passive"))
      (node (ref "J1") (pin "3") (pinfunction "OUT2_3") (pintype "passive"))
      (node (ref "JTAG") (pin "5") (pinfunction "5_5") (pintype "passive"))
      (node (ref "Q1") (pin "2") (pinfunction "S_2") (pintype "passive"))
      (node (ref "R14") (pin "2") (pinfunction "2_2") (pintype "passive"))
      (node (ref "R15") (pin "2") (pinfunction "2_2") (pintype "passive"))
      (node (ref "R38") (pin "2") (pinfunction "2_2") (pintype "passive"))
      (node (ref "R4") (pin "2") (pinfunction "2_2") (pintype "passive"))
      (node (ref "R5") (pin "2") (pinfunction "2_2") (pintype "passive"))
      (node (ref "R6") (pin "2") (pinfunction "2_2") (pintype "passive"))
      (node (ref "R7") (pin "2") (pinfunction "2_2") (pintype "passive"))
      (node (ref "U1") (pin "1") (pinfunction "ADVREF_1") (pintype "input"))
      (node (ref "U1") (pin "18") (pinfunction "VDDIO_18") (pintype "power_in"))
      (node (ref "U1") (pin "45") (pinfunction "VDDIO_45") (pintype "power_in"))
      (node (ref "U1") (pin "58") (pinfunction "VDDIO_58") (pintype "power_in"))
      (node (ref "U1") (pin "59") (pinfunction "VDDFLASH_59") (pintype "power_in"))
      (node (ref "U1") (pin "7") (pinfunction "VDDIN_7") (pintype "power_in"))
      (node (ref "U2") (pin "2") (pinfunction "Vout_2") (pintype "power_in"))
      (node (ref "U2") (pin "4") (pinfunction "TAB_4") (pintype "passive"))
      (node (ref "U5") (pin "8") (pinfunction "VCC_8") (pintype "passive"))
      (node (ref "XBEE") (pin "1") (pinfunction "1_1") (pintype "passive"))
    )
    (net (code "46") (name "5Va") (class "Default")
      (node (ref "C34") (pin "2") (pinfunction "2_2") (pintype "passive"))
      (node (ref "C35") (pin "2") (pinfunction "2_2") (pintype "passive"))
      (node (ref "L8") (pin "2") (pinfunction "2_2") (pintype "passive"))
      (node (ref "U8") (pin "1") (pinfunction "Vin_1") (pintype "passive"))
      (node (ref "U8") (pin "3") (pinfunction "EN_3") (pintype "passive"))
    )
    (net (code "47") (name "5Vb") (class "Default")
      (node (ref "C26") (pin "2") (pinfunction "2_2") (pintype "passive"))
      (node (ref "C8") (pin "2") (pinfunction "2_2") (pintype "passive"))
      (node (ref "D4") (pin "2") (pinfunction "K_2") (pintype "passive"))
      (node (ref "J1") (pin "2") (pinfunction "OUT1_2") (pintype "passive"))
      (node (ref "L7") (pin "2") (pinfunction "2_2") (pintype "passive"))
      (node (ref "U2") (pin "3") (pinfunction "Vin_3") (pintype "power_in"))
    )
    (net (code "48") (name "A3V3") (class "Default")
      (node (ref "C23") (pin "2") (pinfunction "2_2") (pintype "passive"))
      (node (ref "C30") (pin "2") (pinfunction "2_2") (pintype "passive"))
      (node (ref "C37") (pin "2") (pinfunction "2_2") (pintype "passive"))
      (node (ref "C38") (pin "2") (pinfunction "2_2") (pintype "passive"))
      (node (ref "U10") (pin "1") (pinfunction "VDD_1") (pintype "passive"))
      (node (ref "U3") (pin "13") (pinfunction "VDD_13") (pintype "power_in"))
      (node (ref "U8") (pin "4") (pinfunction "Vout_4") (pintype "passive"))
    )
    (net (code "49") (name "AGND") (class "Default")
      (node (ref "C23") (pin "1") (pinfunction "1_1") (pintype "passive"))
      (node (ref "C30") (pin "1") (pinfunction "1_1") (pintype "passive"))
      (node (ref "C36") (pin "1") (pinfunction "1_1") (pintype "passive"))
      (node (ref "C37") (pin "1") (pinfunction "1_1") (pintype "passive"))
      (node (ref "C38") (pin "1") (pinfunction "1_1") (pintype "passive"))
      (node (ref "L3") (pin "2") (pinfunction "2_2") (pintype "passive"))
      (node (ref "L4") (pin "2") (pinfunction "2_2") (pintype "passive"))
      (node (ref "U10") (pin "2") (pinfunction "PS_2") (pintype "passive"))
      (node (ref "U10") (pin "3") (pinfunction "GND_3") (pintype "passive"))
      (node (ref "U3") (pin "18") (pinfunction "GND_18") (pintype "power_in"))
      (node (ref "U8") (pin "2") (pinfunction "GND_2") (pintype "passive"))
    )
    (net (code "50") (name "GND") (class "Default")
      (node (ref "ADC") (pin "2") (pinfunction "GND_2") (pintype "passive"))
      (node (ref "C1") (pin "1") (pinfunction "1_1") (pintype "passive"))
      (node (ref "C10") (pin "1") (pinfunction "1_1") (pintype "passive"))
      (node (ref "C11") (pin "1") (pinfunction "1_1") (pintype "passive"))
      (node (ref "C12") (pin "1") (pinfunction "1_1") (pintype "passive"))
      (node (ref "C13") (pin "1") (pinfunction "1_1") (pintype "passive"))
      (node (ref "C14") (pin "1") (pinfunction "1_1") (pintype "passive"))
      (node (ref "C15") (pin "1") (pinfunction "1_1") (pintype "passive"))
      (node (ref "C16") (pin "1") (pinfunction "1_1") (pintype "passive"))
      (node (ref "C17") (pin "1") (pinfunction "1_1") (pintype "passive"))
      (node (ref "C18") (pin "1") (pinfunction "1_1") (pintype "passive"))
      (node (ref "C19") (pin "1") (pinfunction "1_1") (pintype "passive"))
      (node (ref "C2") (pin "1") (pinfunction "1_1") (pintype "passive"))
      (node (ref "C20") (pin "1") (pinfunction "1_1") (pintype "passive"))
      (node (ref "C21") (pin "1") (pinfunction "1_1") (pintype "passive"))
      (node (ref "C22") (pin "1") (pinfunction "1_1") (pintype "passive"))
      (node (ref "C24") (pin "1") (pinfunction "1_1") (pintype "passive"))
      (node (ref "C25") (pin "1") (pinfunction "1_1") (pintype "passive"))
      (node (ref "C26") (pin "1") (pinfunction "1_1") (pintype "passive"))
      (node (ref "C3") (pin "1") (pinfunction "1_1") (pintype "passive"))
      (node (ref "C31") (pin "1") (pinfunction "1_1") (pintype "passive"))
      (node (ref "C32") (pin "1") (pinfunction "1_1") (pintype "passive"))
      (node (ref "C34") (pin "1") (pinfunction "1_1") (pintype "passive"))
      (node (ref "C35") (pin "1") (pinfunction "1_1") (pintype "passive"))
      (node (ref "C4") (pin "1") (pinfunction "1_1") (pintype "passive"))
      (node (ref "C41") (pin "1") (pinfunction "1_1") (pintype "passive"))
      (node (ref "C5") (pin "1") (pinfunction "1_1") (pintype "passive"))
      (node (ref "C6") (pin "1") (pinfunction "1_1") (pintype "passive"))
      (node (ref "C7") (pin "1") (pinfunction "1_1") (pintype "passive"))
      (node (ref "C8") (pin "1") (pinfunction "1_1") (pintype "passive"))
      (node (ref "C9") (pin "1") (pinfunction "1_1") (pintype "passive"))
      (node (ref "COMPASS") (pin "4") (pinfunction "4_4") (pintype "passive"))
      (node (ref "GPIO") (pin "1") (pinfunction "1_1") (pintype "passive"))
      (node (ref "GPIO") (pin "10") (pinfunction "10_10") (pintype "passive"))
      (node (ref "GPIO") (pin "13") (pinfunction "13_13") (pintype "passive"))
      (node (ref "GPIO") (pin "16") (pinfunction "16_16") (pintype "passive"))
      (node (ref "GPIO") (pin "19") (pinfunction "19_19") (pintype "passive"))
      (node (ref "GPIO") (pin "4") (pinfunction "4_4") (pintype "passive"))
      (node (ref "GPIO") (pin "7") (pinfunction "7_7") (pintype "passive"))
      (node (ref "GPS") (pin "4") (pinfunction "4_4") (pintype "passive"))
      (node (ref "JTAG") (pin "7") (pinfunction "7_7") (pintype "passive"))
      (node (ref "L3") (pin "1") (pinfunction "1_1") (pintype "passive"))
      (node (ref "L4") (pin "1") (pinfunction "1_1") (pintype "passive"))
      (node (ref "MOTORS") (pin "1") (pinfunction "1_1") (pintype "passive"))
      (node (ref "MOTORS") (pin "10") (pinfunction "10_10") (pintype "passive"))
      (node (ref "MOTORS") (pin "4") (pinfunction "4_4") (pintype "passive"))
      (node (ref "MOTORS") (pin "7") (pinfunction "7_7") (pintype "passive"))
      (node (ref "R1") (pin "1") (pinfunction "1_1") (pintype "passive"))
      (node (ref "R2") (pin "1") (pinfunction "1_1") (pintype "passive"))
      (node (ref "R25") (pin "1") (pinfunction "1_1") (pintype "passive"))
      (node (ref "R29") (pin "2") (pinfunction "2_2") (pintype "passive"))
      (node (ref "R30") (pin "2") (pinfunction "2_2") (pintype "passive"))
      (node (ref "R35") (pin "1") (pinfunction "1_1") (pintype "passive"))
      (node (ref "R8") (pin "1") (pinfunction "1_1") (pintype "passive"))
      (node (ref "SW1") (pin "2") (pinfunction "2_2") (pintype "passive"))
      (node (ref "SWITCH") (pin "1") (pinfunction "1_1") (pintype "passive"))
      (node (ref "U1") (pin "17") (pinfunction "GND_17") (pintype "power_in"))
      (node (ref "U1") (pin "2") (pinfunction "GND_2") (pintype "power_in"))
      (node (ref "U1") (pin "3") (pinfunction "AD4_3") (pintype "input"))
      (node (ref "U1") (pin "4") (pinfunction "AD5_4") (pintype "input"))
      (node (ref "U1") (pin "46") (pinfunction "GND_46") (pintype "power_in"))
      (node (ref "U1") (pin "5") (pinfunction "AD6_5") (pintype "input"))
      (node (ref "U1") (pin "50") (pinfunction "JTAGSEL_50") (pintype "input"))
      (node (ref "U1") (pin "60") (pinfunction "GND_60") (pintype "power_in"))
      (node (ref "U2") (pin "1") (pinfunction "GND_1") (pintype "power_in"))
      (node (ref "U3") (pin "1") (pinfunction "CLKIN_1") (pintype "input"))
      (node (ref "U3") (pin "11") (pinfunction "FSYNC_11") (pintype "input"))
      (node (ref "U3") (pin "6") (pinfunction "ES_DA_6") (pintype "bidirectional"))
      (node (ref "U5") (pin "1") (pinfunction "A0_1") (pintype "passive"))
      (node (ref "U5") (pin "2") (pinfunction "A1_2") (pintype "passive"))
      (node (ref "U5") (pin "3") (pinfunction "A2_3") (pintype "passive"))
      (node (ref "U5") (pin "4") (pinfunction "GND_4") (pintype "passive"))
      (node (ref "USB") (pin "5") (pinfunction "GND_5") (pintype "passive"))
      (node (ref "X1") (pin "2") (pinfunction "2_2") (pintype "passive"))
      (node (ref "X1") (pin "4") (pinfunction "4_4") (pintype "passive"))
      (node (ref "XBEE") (pin "4") (pinfunction "4_4") (pintype "passive"))
    )
    (net (code "51") (name "Net-(C18-Pad2)") (class "Default")
      (node (ref "C18") (pin "2") (pinfunction "2_2") (pintype "passive"))
      (node (ref "R3") (pin "1") (pinfunction "1_1") (pintype "passive"))
    )
    (net (code "52") (name "Net-(D1-K)") (class "Default")
      (node (ref "D1") (pin "2") (pinfunction "K_2") (pintype "passive"))
      (node (ref "R1") (pin "2") (pinfunction "2_2") (pintype "passive"))
    )
    (net (code "53") (name "Net-(D2-K)") (class "Default")
      (node (ref "D2") (pin "2") (pinfunction "K_2") (pintype "passive"))
      (node (ref "R10") (pin "2") (pinfunction "2_2") (pintype "passive"))
    )
    (net (code "54") (name "Net-(D3-K)") (class "Default")
      (node (ref "D3") (pin "2") (pinfunction "K_2") (pintype "passive"))
      (node (ref "R11") (pin "2") (pinfunction "2_2") (pintype "passive"))
    )
    (net (code "55") (name "Net-(D4-A)") (class "Default")
      (node (ref "D4") (pin "1") (pinfunction "A_1") (pintype "passive"))
      (node (ref "R34") (pin "1") (pinfunction "1_1") (pintype "passive"))
      (node (ref "USB") (pin "1") (pinfunction "VCC(5V)_1") (pintype "power_in"))
    )
    (net (code "56") (name "Net-(GPIO-Pad3)") (class "Default")
      (node (ref "GPIO") (pin "3") (pinfunction "3_3") (pintype "passive"))
      (node (ref "R12") (pin "2") (pinfunction "2_2") (pintype "passive"))
    )
    (net (code "57") (name "Net-(GPIO-Pad6)") (class "Default")
      (node (ref "GPIO") (pin "6") (pinfunction "6_6") (pintype "passive"))
      (node (ref "R16") (pin "2") (pinfunction "2_2") (pintype "passive"))
    )
    (net (code "58") (name "Net-(GPIO-Pad9)") (class "Default")
      (node (ref "GPIO") (pin "9") (pinfunction "9_9") (pintype "passive"))
      (node (ref "R18") (pin "2") (pinfunction "2_2") (pintype "passive"))
    )
    (net (code "59") (name "Net-(GPIO-Pad12)") (class "Default")
      (node (ref "GPIO") (pin "12") (pinfunction "12_12") (pintype "passive"))
      (node (ref "R19") (pin "2") (pinfunction "2_2") (pintype "passive"))
    )
    (net (code "60") (name "Net-(GPIO-Pad15)") (class "Default")
      (node (ref "GPIO") (pin "15") (pinfunction "15_15") (pintype "passive"))
      (node (ref "R20") (pin "2") (pinfunction "2_2") (pintype "passive"))
    )
    (net (code "61") (name "Net-(GPIO-Pad18)") (class "Default")
      (node (ref "GPIO") (pin "18") (pinfunction "18_18") (pintype "passive"))
      (node (ref "R22") (pin "2") (pinfunction "2_2") (pintype "passive"))
    )
    (net (code "62") (name "Net-(GPIO-Pad21)") (class "Default")
      (node (ref "GPIO") (pin "21") (pinfunction "21_21") (pintype "passive"))
      (node (ref "R23") (pin "2") (pinfunction "2_2") (pintype "passive"))
    )
    (net (code "63") (name "Net-(J1-IN)") (class "Default")
      (node (ref "C21") (pin "2") (pinfunction "2_2") (pintype "passive"))
      (node (ref "GPS") (pin "1") (pinfunction "1_1") (pintype "passive"))
      (node (ref "J1") (pin "1") (pinfunction "IN_1") (pintype "passive"))
    )
    (net (code "64") (name "Net-(MOTORS-Pad3)") (class "Default")
      (node (ref "MOTORS") (pin "3") (pinfunction "3_3") (pintype "passive"))
      (node (ref "R9") (pin "2") (pinfunction "2_2") (pintype "passive"))
    )
    (net (code "65") (name "Net-(MOTORS-Pad6)") (class "Default")
      (node (ref "MOTORS") (pin "6") (pinfunction "6_6") (pintype "passive"))
      (node (ref "R13") (pin "2") (pinfunction "2_2") (pintype "passive"))
    )
    (net (code "66") (name "Net-(MOTORS-Pad9)") (class "Default")
      (node (ref "MOTORS") (pin "9") (pinfunction "9_9") (pintype "passive"))
      (node (ref "R17") (pin "2") (pinfunction "2_2") (pintype "passive"))
    )
    (net (code "67") (name "Net-(MOTORS-Pad12)") (class "Default")
      (node (ref "MOTORS") (pin "12") (pinfunction "12_12") (pintype "passive"))
      (node (ref "R21") (pin "2") (pinfunction "2_2") (pintype "passive"))
    )
    (net (code "68") (name "Net-(Q1-D)") (class "Default")
      (node (ref "Q1") (pin "1") (pinfunction "D_1") (pintype "passive"))
      (node (ref "R33") (pin "1") (pinfunction "1_1") (pintype "passive"))
    )
    (net (code "69") (name "Net-(R26-Pad1)") (class "Default")
      (node (ref "R26") (pin "1") (pinfunction "1_1") (pintype "passive"))
      (node (ref "U10") (pin "5") (pinfunction "CSB_5") (pintype "passive"))
    )
    (net (code "70") (name "Net-(R37-Pad1)") (class "Default")
      (node (ref "R37") (pin "1") (pinfunction "1_1") (pintype "passive"))
      (node (ref "SWITCH") (pin "2") (pinfunction "2_2") (pintype "passive"))
    )
    (net (code "71") (name "Net-(U3-CPOUT)") (class "Default")
      (node (ref "C25") (pin "2") (pinfunction "2_2") (pintype "passive"))
      (node (ref "U3") (pin "20") (pinfunction "CPOUT_20") (pintype "passive"))
    )
    (net (code "72") (name "Net-(U3-CS)") (class "Default")
      (node (ref "R36") (pin "1") (pinfunction "1_1") (pintype "passive"))
      (node (ref "U3") (pin "8") (pinfunction "CS_8") (pintype "passive"))
    )
    (net (code "73") (name "Net-(U3-REGOUT)") (class "Default")
      (node (ref "C24") (pin "2") (pinfunction "2_2") (pintype "passive"))
      (node (ref "U3") (pin "10") (pinfunction "REGOUT_10") (pintype "passive"))
    )
    (net (code "74") (name "Net-(U3-SCLK)") (class "Default")
      (node (ref "R36") (pin "4") (pinfunction "4_4") (pintype "passive"))
      (node (ref "U3") (pin "23") (pinfunction "SCLK_23") (pintype "input"))
    )
    (net (code "75") (name "Net-(U3-SDI)") (class "Default")
      (node (ref "R36") (pin "3") (pinfunction "3_3") (pintype "passive"))
      (node (ref "U3") (pin "24") (pinfunction "SDI_24") (pintype "bidirectional"))
    )
    (net (code "76") (name "Net-(U3-SDO)") (class "Default")
      (node (ref "R36") (pin "2") (pinfunction "2_2") (pintype "passive"))
      (node (ref "U3") (pin "9") (pinfunction "SDO_9") (pintype "input"))
    )
    (net (code "77") (name "Net-(U8-BP)") (class "Default")
      (node (ref "C36") (pin "2") (pinfunction "2_2") (pintype "passive"))
      (node (ref "U8") (pin "5") (pinfunction "BP_5") (pintype "passive"))
    )
    (net (code "78") (name "Net-(U10-SCLK)") (class "Default")
      (node (ref "R26") (pin "4") (pinfunction "4_4") (pintype "passive"))
      (node (ref "U10") (pin "8") (pinfunction "SCLK_8") (pintype "passive"))
    )
    (net (code "79") (name "Net-(U10-SDI{slash}SDA)") (class "Default")
      (node (ref "R26") (pin "3") (pinfunction "3_3") (pintype "passive"))
      (node (ref "U10") (pin "7") (pinfunction "SDI/SDA_7") (pintype "passive"))
    )
    (net (code "80") (name "Net-(U10-SDO)") (class "Default")
      (node (ref "R26") (pin "2") (pinfunction "2_2") (pintype "passive"))
      (node (ref "U10") (pin "6") (pinfunction "SDO_6") (pintype "passive"))
    )
    (net (code "81") (name "Net-(USB-D+)") (class "Default")
      (node (ref "R30") (pin "1") (pinfunction "1_1") (pintype "passive"))
      (node (ref "R32") (pin "1") (pinfunction "1_1") (pintype "passive"))
      (node (ref "R33") (pin "2") (pinfunction "2_2") (pintype "passive"))
      (node (ref "USB") (pin "3") (pinfunction "D+_3") (pintype "bidirectional"))
    )
    (net (code "82") (name "Net-(USB-D-)") (class "Default")
      (node (ref "R29") (pin "1") (pinfunction "1_1") (pintype "passive"))
      (node (ref "R31") (pin "1") (pinfunction "1_1") (pintype "passive"))
      (node (ref "USB") (pin "2") (pinfunction "D-_2") (pintype "bidirectional"))
    )
    (net (code "83") (name "unconnected-(JTAG-Pad6)") (class "Default")
      (node (ref "JTAG") (pin "6") (pinfunction "6_6") (pintype "passive"))
    )
    (net (code "84") (name "unconnected-(SW1-Pad1)") (class "Default")
      (node (ref "SW1") (pin "1") (pinfunction "1_1") (pintype "passive"))
    )
    (net (code "85") (name "unconnected-(SW1-Pad4)") (class "Default")
      (node (ref "SW1") (pin "4") (pinfunction "4_4") (pintype "passive"))
    )
    (net (code "86") (name "unconnected-(U1A-PA16{slash}PGMD4{slash}TK{slash}TIOB1-Pad19)") (class "Default")
      (node (ref "U1") (pin "19") (pinfunction "PA16/PGMD4/TK/TIOB1_19") (pintype "bidirectional"))
    )
    (net (code "87") (name "unconnected-(U1A-PA19{slash}PGMD7{slash}AD2{slash}RK{slash}FIQ{slash}AD2-Pad13)") (class "Default")
      (node (ref "U1") (pin "13") (pinfunction "PA19/PGMD7/AD2/RK/FIQ/AD2_13") (pintype "bidirectional"))
    )
    (net (code "88") (name "unconnected-(U1A-PA28{slash}DSR1{slash}TCLK1-Pad38)") (class "Default")
      (node (ref "U1") (pin "38") (pinfunction "PA28/DSR1/TCLK1_38") (pintype "bidirectional"))
    )
    (net (code "89") (name "unconnected-(U1A-PA31{slash}NPCS1{slash}PCK2-Pad52)") (class "Default")
      (node (ref "U1") (pin "52") (pinfunction "PA31/NPCS1/PCK2_52") (pintype "bidirectional"))
    )
    (net (code "90") (name "unconnected-(U2-NC-Pad4)") (class "Default")
      (node (ref "U2") (pin "4") (pinfunction "NC_4") (pintype "passive"))
    )
    (net (code "91") (name "unconnected-(U3-ES_CL-Pad7)") (class "Default")
      (node (ref "U3") (pin "7") (pinfunction "ES_CL_7") (pintype "output"))
    )
    (net (code "92") (name "unconnected-(U3-INT-Pad12)") (class "Default")
      (node (ref "U3") (pin "12") (pinfunction "INT_12") (pintype "output"))
    )
    (net (code "93") (name "unconnected-(U3-NC-Pad2)") (class "Default")
      (node (ref "U3") (pin "2") (pinfunction "NC_2") (pintype "passive"))
    )
    (net (code "94") (name "unconnected-(U3-NC-Pad4)") (class "Default")
      (node (ref "U3") (pin "4") (pinfunction "NC_4") (pintype "passive"))
    )
    (net (code "95") (name "unconnected-(U3-NC-Pad5)") (class "Default")
      (node (ref "U3") (pin "5") (pinfunction "NC_5") (pintype "passive"))
    )
    (net (code "96") (name "unconnected-(U3-NC-Pad14)") (class "Default")
      (node (ref "U3") (pin "14") (pinfunction "NC_14") (pintype "passive"))
    )
    (net (code "97") (name "unconnected-(U3-NC-Pad16)") (class "Default")
      (node (ref "U3") (pin "16") (pinfunction "NC_16") (pintype "passive"))
    )
    (net (code "98") (name "unconnected-(U3-NC-Pad19)") (class "Default")
      (node (ref "U3") (pin "19") (pinfunction "NC_19") (pintype "passive"))
    )
    (net (code "99") (name "unconnected-(U3-NC-Pad21)") (class "Default")
      (node (ref "U3") (pin "21") (pinfunction "NC_21") (pintype "passive"))
    )
    (net (code "100") (name "unconnected-(U3-NC-Pad22)") (class "Default")
      (node (ref "U3") (pin "22") (pinfunction "NC_22") (pintype "passive"))
    )
    (net (code "101") (name "unconnected-(U5-WP-Pad7)") (class "Default")
      (node (ref "U5") (pin "7") (pinfunction "WP_7") (pintype "passive"))
    )
    (net (code "102") (name "unconnected-(U10-CSB-Pad4)") (class "Default")
      (node (ref "U10") (pin "4") (pinfunction "CSB_4") (pintype "passive"))
    )
    (net (code "103") (name "unconnected-(USB-NC-Pad4)") (class "Default")
      (node (ref "USB") (pin "4") (pinfunction "NC_4") (pintype "passive"))
    )
  )
)
